# V1.net
KiCad netlist of a schematic drawn in EAGLE
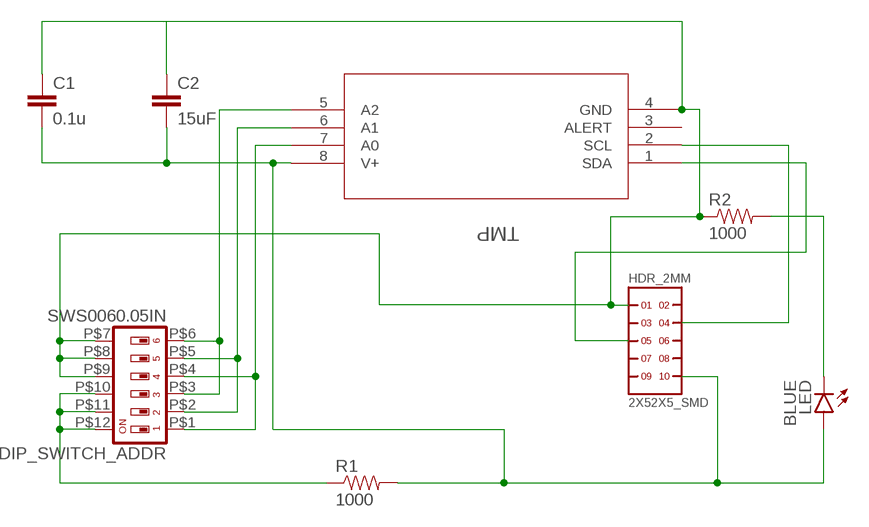
[diagram p0: schematic, sheet 1]

(export (version "E")
  (design (tool "Eeschema 10.0.6"))
  (components
    (comp (ref "C1")
      (value "0.1u")
      (footprint "eagle-import:0805")
      (libsource (lib "eagle-import") (part "22UF-6.3V-20%(0805)"))
    )
    (comp (ref "C2")
      (value "15uF")
      (footprint "eagle-import:0805-CAP")
      (libsource (lib "eagle-import") (part "1.0UF-25V-+80/-20(0805){dblquote}"))
    )
    (comp (ref "DIP_SWITCH_ADDR")
      (value "SWS0060.05IN")
      (footprint "eagle-import:SMS-006")
      (libsource (lib "eagle-import") (part "SWS0060.05IN"))
    )
    (comp (ref "HDR_2MM")
      (value "2X52X5_SMD")
      (footprint "eagle-import:2X5")
      (libsource (lib "eagle-import") (part "2X52X5_SMD"))
    )
    (comp (ref "LED")
      (value "BLUE")
      (footprint "eagle-import:LED-1206")
      (libsource (lib "eagle-import") (part "LED-BLUE1206"))
    )
    (comp (ref "R1")
      (value "1000")
      (footprint "eagle-import:0805")
      (libsource (lib "eagle-import") (part "RESISTOR0805-RES"))
    )
    (comp (ref "R2")
      (value "1000")
      (footprint "eagle-import:0805")
      (libsource (lib "eagle-import") (part "RESISTOR0805-RES"))
    )
    (comp (ref "TMP")
      (value "TMP175_DGK_8")
      (footprint "eagle-import:DGK8")
      (fields
        (field (name "GENERIC_PART_NUMBER") "TMP175")
        (field (name "MANUFACTURER") "Texas Instruments")
        (field (name "MANUFACTURER_PART_NUMBER") "tmp175_dgk_8")
      )
      (libsource (lib "eagle-import") (part "TMP175_DGK_8"))
    )
  )
  (nets
    (net (code "1") (name "Net-(DIP_SWITCH_ADDR-1)") (class "Default")
      (node (ref "DIP_SWITCH_ADDR") (pin "P$1") (pinfunction "1_P$1") (pintype "passive"))
      (node (ref "DIP_SWITCH_ADDR") (pin "P$4") (pinfunction "4_P$4") (pintype "passive"))
      (node (ref "TMP") (pin "7") (pinfunction "A0_7") (pintype "bidirectional"))
    )
    (net (code "2") (name "Net-(DIP_SWITCH_ADDR-2)") (class "Default")
      (node (ref "DIP_SWITCH_ADDR") (pin "P$2") (pinfunction "2_P$2") (pintype "passive"))
      (node (ref "DIP_SWITCH_ADDR") (pin "P$5") (pinfunction "5_P$5") (pintype "passive"))
      (node (ref "TMP") (pin "6") (pinfunction "A1_6") (pintype "bidirectional"))
    )
    (net (code "3") (name "Net-(DIP_SWITCH_ADDR-3)") (class "Default")
      (node (ref "DIP_SWITCH_ADDR") (pin "P$3") (pinfunction "3_P$3") (pintype "passive"))
      (node (ref "DIP_SWITCH_ADDR") (pin "P$6") (pinfunction "6_P$6") (pintype "passive"))
      (node (ref "TMP") (pin "5") (pinfunction "A2_5") (pintype "bidirectional"))
    )
    (net (code "4") (name "Net-(DIP_SWITCH_ADDR-7)") (class "Default")
      (node (ref "C1") (pin "1") (pinfunction "1_1") (pintype "passive"))
      (node (ref "C2") (pin "1") (pinfunction "1_1") (pintype "passive"))
      (node (ref "DIP_SWITCH_ADDR") (pin "P$7") (pinfunction "7_P$7") (pintype "passive"))
      (node (ref "DIP_SWITCH_ADDR") (pin "P$8") (pinfunction "8_P$8") (pintype "passive"))
      (node (ref "DIP_SWITCH_ADDR") (pin "P$9") (pinfunction "9_P$9") (pintype "passive"))
      (node (ref "HDR_2MM") (pin "P$1") (pinfunction "1_P$1") (pintype "bidirectional"))
      (node (ref "R2") (pin "1") (pinfunction "1_1") (pintype "passive"))
      (node (ref "TMP") (pin "4") (pinfunction "GND_4") (pintype "power_in"))
    )
    (net (code "5") (name "Net-(DIP_SWITCH_ADDR-10)") (class "Default")
      (node (ref "DIP_SWITCH_ADDR") (pin "P$10") (pinfunction "10_P$10") (pintype "passive"))
      (node (ref "DIP_SWITCH_ADDR") (pin "P$11") (pinfunction "11_P$11") (pintype "passive"))
      (node (ref "DIP_SWITCH_ADDR") (pin "P$12") (pinfunction "12_P$12") (pintype "passive"))
      (node (ref "R1") (pin "1") (pinfunction "1_1") (pintype "passive"))
    )
    (net (code "6") (name "Net-(HDR_2MM-4)") (class "Default")
      (node (ref "HDR_2MM") (pin "P$4") (pinfunction "4_P$4") (pintype "bidirectional"))
      (node (ref "TMP") (pin "2") (pinfunction "SCL_2") (pintype "bidirectional"))
    )
    (net (code "7") (name "Net-(HDR_2MM-5)") (class "Default")
      (node (ref "HDR_2MM") (pin "P$5") (pinfunction "5_P$5") (pintype "bidirectional"))
      (node (ref "TMP") (pin "1") (pinfunction "SDA_1") (pintype "bidirectional"))
    )
    (net (code "8") (name "Net-(HDR_2MM-10)") (class "Default")
      (node (ref "C1") (pin "2") (pinfunction "2_2") (pintype "passive"))
      (node (ref "C2") (pin "2") (pinfunction "2_2") (pintype "passive"))
      (node (ref "HDR_2MM") (pin "P$10") (pinfunction "10_P$10") (pintype "bidirectional"))
      (node (ref "LED") (pin "A") (pinfunction "A_A") (pintype "passive"))
      (node (ref "R1") (pin "2") (pinfunction "2_2") (pintype "passive"))
      (node (ref "TMP") (pin "8") (pinfunction "V+_8") (pintype "power_in"))
    )
    (net (code "9") (name "Net-(LED-PadC)") (class "Default")
      (node (ref "LED") (pin "C") (pinfunction "C_C") (pintype "passive"))
      (node (ref "R2") (pin "2") (pinfunction "2_2") (pintype "passive"))
    )
    (net (code "10") (name "unconnected-(HDR_2MM-2-PadP$2)") (class "Default")
      (node (ref "HDR_2MM") (pin "P$2") (pinfunction "2_P$2") (pintype "bidirectional"))
    )
    (net (code "11") (name "unconnected-(HDR_2MM-3-PadP$3)") (class "Default")
      (node (ref "HDR_2MM") (pin "P$3") (pinfunction "3_P$3") (pintype "bidirectional"))
    )
    (net (code "12") (name "unconnected-(HDR_2MM-6-PadP$6)") (class "Default")
      (node (ref "HDR_2MM") (pin "P$6") (pinfunction "6_P$6") (pintype "bidirectional"))
    )
    (net (code "13") (name "unconnected-(HDR_2MM-7-PadP$7)") (class "Default")
      (node (ref "HDR_2MM") (pin "P$7") (pinfunction "7_P$7") (pintype "bidirectional"))
    )
    (net (code "14") (name "unconnected-(HDR_2MM-8-PadP$8)") (class "Default")
      (node (ref "HDR_2MM") (pin "P$8") (pinfunction "8_P$8") (pintype "bidirectional"))
    )
    (net (code "15") (name "unconnected-(HDR_2MM-9-PadP$9)") (class "Default")
      (node (ref "HDR_2MM") (pin "P$9") (pinfunction "9_P$9") (pintype "bidirectional"))
    )
    (net (code "16") (name "unconnected-(TMP-ALERT-Pad3)") (class "Default")
      (node (ref "TMP") (pin "3") (pinfunction "ALERT_3") (pintype "bidirectional"))
    )
  )
)
